# ir_module.net
KiCad netlist of a schematic drawn in EAGLE
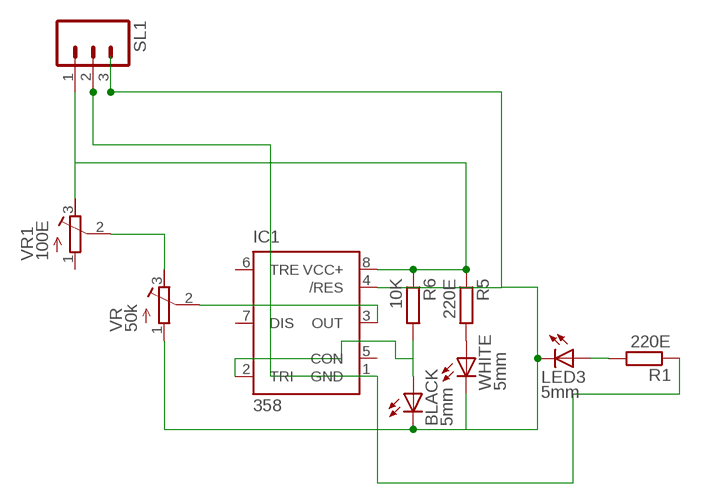
[diagram p0: schematic, sheet 1]

(export (version "E")
  (design (tool "Eeschema 10.0.6"))
  (components
    (comp (ref "BLACK")
      (value "5mm")
      (footprint "eagle-import:LED5MM")
      (libsource (lib "eagle-import") (part "LED5MM"))
    )
    (comp (ref "IC1")
      (value "358")
      (footprint "eagle-import:DIL-08")
      (fields (field (name "MF") "Arrow Electronics") (field (name "MPN") "NE555N"))
      (libsource (lib "eagle-import") (part "NE555"))
    )
    (comp (ref "LED3")
      (value "5mm")
      (footprint "eagle-import:LED5MM")
      (libsource (lib "eagle-import") (part "LED5MM"))
    )
    (comp (ref "R1")
      (value "220E")
      (footprint "eagle-import:0204_7")
      (libsource (lib "eagle-import") (part "R-EU_0204/7"))
    )
    (comp (ref "R5")
      (value "220E")
      (footprint "eagle-import:0204_7")
      (libsource (lib "eagle-import") (part "R-EU_0204/7"))
    )
    (comp (ref "R6")
      (value "10K")
      (footprint "eagle-import:0204_7")
      (libsource (lib "eagle-import") (part "R-EU_0204/7"))
    )
    (comp (ref "SL1")
      (value "M03")
      (footprint "eagle-import:03P")
      (libsource (lib "eagle-import") (part "M03"))
    )
    (comp (ref "VR")
      (value "50k")
      (footprint "eagle-import:RTRIM64P")
      (libsource (lib "eagle-import") (part "R-TRIMM64P"))
    )
    (comp (ref "VR1")
      (value "100E")
      (footprint "eagle-import:RTRIM64P")
      (libsource (lib "eagle-import") (part "R-TRIMM64P"))
    )
    (comp (ref "WHITE")
      (value "5mm")
      (footprint "eagle-import:LED5MM")
      (libsource (lib "eagle-import") (part "LED5MM"))
    )
  )
  (nets
    (net (code "1") (name "Net-(BLACK-C)") (class "Default")
      (node (ref "BLACK") (pin "K") (pinfunction "C_K") (pintype "passive"))
      (node (ref "IC1") (pin "4") (pinfunction "/RES_4") (pintype "input"))
      (node (ref "LED3") (pin "K") (pinfunction "C_K") (pintype "passive"))
      (node (ref "SL1") (pin "3") (pinfunction "3_3") (pintype "passive"))
      (node (ref "VR") (pin "1") (pinfunction "E_1") (pintype "passive"))
      (node (ref "WHITE") (pin "K") (pinfunction "C_K") (pintype "passive"))
    )
    (net (code "2") (name "Net-(IC1-GND)") (class "Default")
      (node (ref "IC1") (pin "1") (pinfunction "GND_1") (pintype "power_in"))
      (node (ref "R1") (pin "1") (pinfunction "1_1") (pintype "passive"))
      (node (ref "SL1") (pin "2") (pinfunction "2_2") (pintype "passive"))
    )
    (net (code "3") (name "Net-(IC1-OUT)") (class "Default")
      (node (ref "IC1") (pin "3") (pinfunction "OUT_3") (pintype "output"))
      (node (ref "VR") (pin "2") (pinfunction "S_2") (pintype "passive"))
    )
    (net (code "4") (name "Net-(IC1-TRI)") (class "Default")
      (node (ref "BLACK") (pin "A") (pinfunction "A_A") (pintype "passive"))
      (node (ref "IC1") (pin "2") (pinfunction "TRI_2") (pintype "input"))
      (node (ref "R6") (pin "2") (pinfunction "2_2") (pintype "passive"))
    )
    (net (code "5") (name "Net-(IC1-VCC+)") (class "Default")
      (node (ref "IC1") (pin "8") (pinfunction "VCC+_8") (pintype "power_in"))
      (node (ref "R5") (pin "1") (pinfunction "1_1") (pintype "passive"))
      (node (ref "R6") (pin "1") (pinfunction "1_1") (pintype "passive"))
      (node (ref "SL1") (pin "1") (pinfunction "1_1") (pintype "passive"))
      (node (ref "VR1") (pin "3") (pinfunction "A_3") (pintype "passive"))
    )
    (net (code "6") (name "Net-(LED3-PadA)") (class "Default")
      (node (ref "LED3") (pin "A") (pinfunction "A_A") (pintype "passive"))
      (node (ref "R1") (pin "2") (pinfunction "2_2") (pintype "passive"))
    )
    (net (code "7") (name "Net-(R5-Pad2)") (class "Default")
      (node (ref "R5") (pin "2") (pinfunction "2_2") (pintype "passive"))
      (node (ref "WHITE") (pin "A") (pinfunction "A_A") (pintype "passive"))
    )
    (net (code "8") (name "Net-(VR-A)") (class "Default")
      (node (ref "VR") (pin "3") (pinfunction "A_3") (pintype "passive"))
      (node (ref "VR1") (pin "2") (pinfunction "S_2") (pintype "passive"))
    )
    (net (code "9") (name "unconnected-(IC1-CON-Pad5)") (class "Default")
      (node (ref "IC1") (pin "5") (pinfunction "CON_5") (pintype "input"))
    )
    (net (code "10") (name "unconnected-(IC1-DIS-Pad7)") (class "Default")
      (node (ref "IC1") (pin "7") (pinfunction "DIS_7") (pintype "input"))
    )
    (net (code "11") (name "unconnected-(IC1-TRE-Pad6)") (class "Default")
      (node (ref "IC1") (pin "6") (pinfunction "TRE_6") (pintype "input"))
    )
    (net (code "12") (name "unconnected-(VR1-E-Pad1)") (class "Default")
      (node (ref "VR1") (pin "1") (pinfunction "E_1") (pintype "passive"))
    )
  )
)
